# IO_ENC.net
KiCad netlist of a schematic drawn in Altium Designer
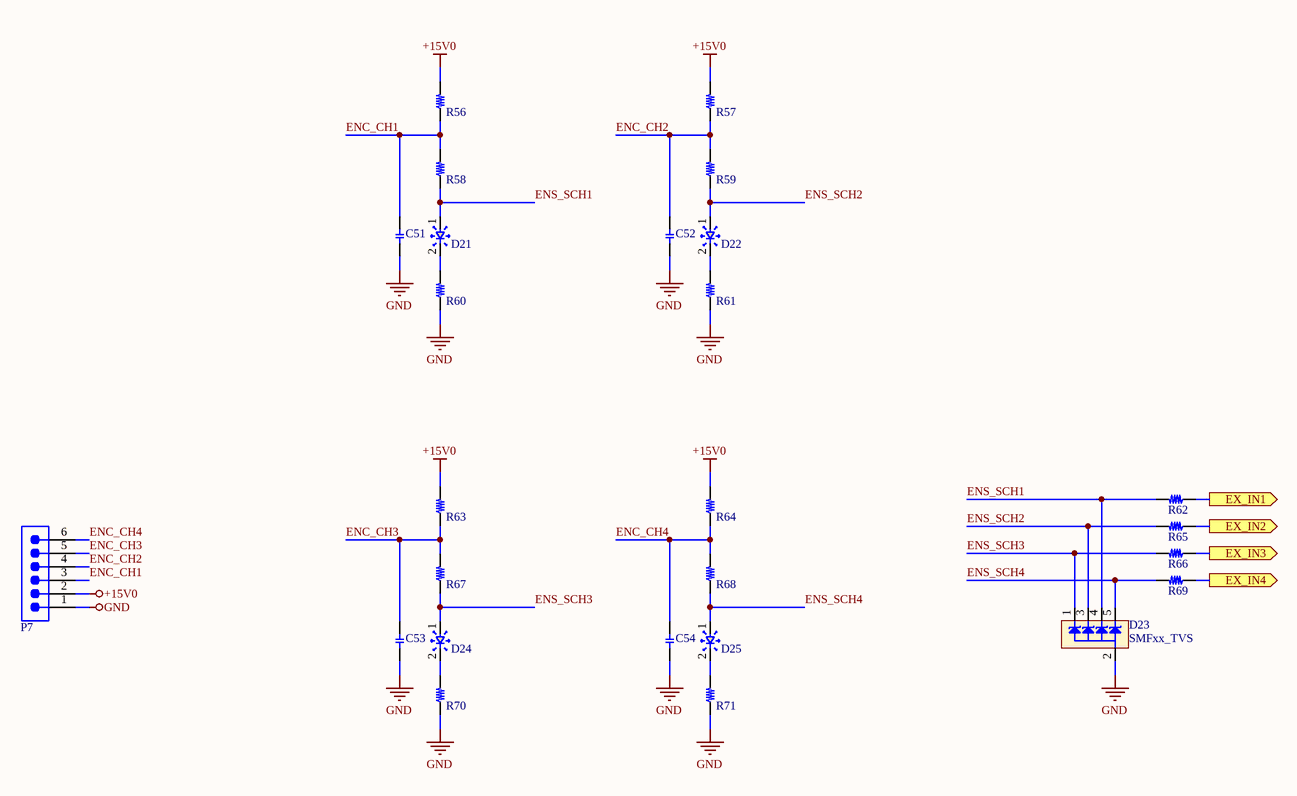
[diagram p0: IO_ENC.SchDoc]

(export (version "E")
  (design (tool "Eeschema 10.0.6"))
  (components
    (comp (ref "C51")
      (value "CAP_SMD")
      (footprint "C 0603")
      (libsource (lib "radmehr_library") (part "CAP_SMD"))
    )
    (comp (ref "C52")
      (value "CAP_SMD")
      (footprint "C 0603")
      (libsource (lib "radmehr_library") (part "CAP_SMD"))
    )
    (comp (ref "C53")
      (value "CAP_SMD")
      (footprint "C 0603")
      (libsource (lib "radmehr_library") (part "CAP_SMD"))
    )
    (comp (ref "C54")
      (value "CAP_SMD")
      (footprint "C 0603")
      (libsource (lib "radmehr_library") (part "CAP_SMD"))
    )
    (comp (ref "D21")
      (value "LED_SMD")
      (footprint "D 0603")
      (libsource (lib "radmehr_library") (part "LED_SMD"))
    )
    (comp (ref "D22")
      (value "LED_SMD")
      (footprint "D 0603")
      (libsource (lib "radmehr_library") (part "LED_SMD"))
    )
    (comp (ref "D23")
      (value "SMFxx_TVS")
      (footprint "SOT353-5")
      (libsource (lib "radmehr_library") (part "SMFxx_TVS"))
    )
    (comp (ref "D24")
      (value "LED_SMD")
      (footprint "D 0603")
      (libsource (lib "radmehr_library") (part "LED_SMD"))
    )
    (comp (ref "D25")
      (value "LED_SMD")
      (footprint "D 0603")
      (libsource (lib "radmehr_library") (part "LED_SMD"))
    )
    (comp (ref "P7")
      (value "691321300006")
      (footprint "691321300006")
      (description "WR-TBL Series 321 Vertical PCB Header, Through Hole, pitch 3.81mm, 6p")
      (fields (field (name "MANUFACTURER") "Wurth Elektronik"))
      (libsource (lib "Altium_WR-TBL (rev22a)") (part "691321300006"))
    )
    (comp (ref "R56")
      (value "RES_SMD")
      (footprint "R 1206")
      (libsource (lib "radmehr_library") (part "RES_SMD"))
    )
    (comp (ref "R57")
      (value "RES_SMD")
      (footprint "R 1206")
      (libsource (lib "radmehr_library") (part "RES_SMD"))
    )
    (comp (ref "R58")
      (value "RES_SMD")
      (footprint "R 0603")
      (libsource (lib "radmehr_library") (part "RES_SMD"))
    )
    (comp (ref "R59")
      (value "RES_SMD")
      (footprint "R 0603")
      (libsource (lib "radmehr_library") (part "RES_SMD"))
    )
    (comp (ref "R60")
      (value "RES_SMD")
      (footprint "R 0603")
      (libsource (lib "radmehr_library") (part "RES_SMD"))
    )
    (comp (ref "R61")
      (value "RES_SMD")
      (footprint "R 0603")
      (libsource (lib "radmehr_library") (part "RES_SMD"))
    )
    (comp (ref "R62")
      (value "RES_SMD")
      (footprint "R 0603")
      (libsource (lib "radmehr_library") (part "RES_SMD"))
    )
    (comp (ref "R63")
      (value "RES_SMD")
      (footprint "R 1206")
      (libsource (lib "radmehr_library") (part "RES_SMD"))
    )
    (comp (ref "R64")
      (value "RES_SMD")
      (footprint "R 1206")
      (libsource (lib "radmehr_library") (part "RES_SMD"))
    )
    (comp (ref "R65")
      (value "RES_SMD")
      (footprint "R 0603")
      (libsource (lib "radmehr_library") (part "RES_SMD"))
    )
    (comp (ref "R66")
      (value "RES_SMD")
      (footprint "R 0603")
      (libsource (lib "radmehr_library") (part "RES_SMD"))
    )
    (comp (ref "R67")
      (value "RES_SMD")
      (footprint "R 0603")
      (libsource (lib "radmehr_library") (part "RES_SMD"))
    )
    (comp (ref "R68")
      (value "RES_SMD")
      (footprint "R 0603")
      (libsource (lib "radmehr_library") (part "RES_SMD"))
    )
    (comp (ref "R69")
      (value "RES_SMD")
      (footprint "R 0603")
      (libsource (lib "radmehr_library") (part "RES_SMD"))
    )
    (comp (ref "R70")
      (value "RES_SMD")
      (footprint "R 0603")
      (libsource (lib "radmehr_library") (part "RES_SMD"))
    )
    (comp (ref "R71")
      (value "RES_SMD")
      (footprint "R 0603")
      (libsource (lib "radmehr_library") (part "RES_SMD"))
    )
  )
  (nets
    (net (code "1") (name "+15V0") (class "Default")
      (node (ref "P7") (pin "2") (pinfunction "2_2") (pintype "passive"))
      (node (ref "R56") (pin "2") (pinfunction "2_2") (pintype "passive"))
      (node (ref "R57") (pin "2") (pinfunction "2_2") (pintype "passive"))
      (node (ref "R63") (pin "2") (pinfunction "2_2") (pintype "passive"))
      (node (ref "R64") (pin "2") (pinfunction "2_2") (pintype "passive"))
    )
    (net (code "2") (name "/ENC_CH1") (class "Default")
      (node (ref "C51") (pin "2") (pinfunction "2_2") (pintype "passive"))
      (node (ref "P7") (pin "3") (pinfunction "3_3") (pintype "passive"))
      (node (ref "R56") (pin "1") (pinfunction "1_1") (pintype "passive"))
      (node (ref "R58") (pin "2") (pinfunction "2_2") (pintype "passive"))
    )
    (net (code "3") (name "/ENC_CH2") (class "Default")
      (node (ref "C52") (pin "2") (pinfunction "2_2") (pintype "passive"))
      (node (ref "P7") (pin "4") (pinfunction "4_4") (pintype "passive"))
      (node (ref "R57") (pin "1") (pinfunction "1_1") (pintype "passive"))
      (node (ref "R59") (pin "2") (pinfunction "2_2") (pintype "passive"))
    )
    (net (code "4") (name "/ENC_CH3") (class "Default")
      (node (ref "C53") (pin "2") (pinfunction "2_2") (pintype "passive"))
      (node (ref "P7") (pin "5") (pinfunction "5_5") (pintype "passive"))
      (node (ref "R63") (pin "1") (pinfunction "1_1") (pintype "passive"))
      (node (ref "R67") (pin "2") (pinfunction "2_2") (pintype "passive"))
    )
    (net (code "5") (name "/ENC_CH4") (class "Default")
      (node (ref "C54") (pin "2") (pinfunction "2_2") (pintype "passive"))
      (node (ref "P7") (pin "6") (pinfunction "6_6") (pintype "passive"))
      (node (ref "R64") (pin "1") (pinfunction "1_1") (pintype "passive"))
      (node (ref "R68") (pin "2") (pinfunction "2_2") (pintype "passive"))
    )
    (net (code "6") (name "/ENS_SCH1") (class "Default")
      (node (ref "D21") (pin "1") (pintype "passive"))
      (node (ref "D23") (pin "4") (pinfunction "K3_4") (pintype "passive"))
      (node (ref "R58") (pin "1") (pinfunction "1_1") (pintype "passive"))
      (node (ref "R62") (pin "2") (pinfunction "2_2") (pintype "passive"))
    )
    (net (code "7") (name "/ENS_SCH2") (class "Default")
      (node (ref "D22") (pin "1") (pintype "passive"))
      (node (ref "D23") (pin "3") (pinfunction "K2_3") (pintype "passive"))
      (node (ref "R59") (pin "1") (pinfunction "1_1") (pintype "passive"))
      (node (ref "R65") (pin "2") (pinfunction "2_2") (pintype "passive"))
    )
    (net (code "8") (name "/ENS_SCH3") (class "Default")
      (node (ref "D23") (pin "1") (pinfunction "K1_1") (pintype "passive"))
      (node (ref "D24") (pin "1") (pintype "passive"))
      (node (ref "R66") (pin "2") (pinfunction "2_2") (pintype "passive"))
      (node (ref "R67") (pin "1") (pinfunction "1_1") (pintype "passive"))
    )
    (net (code "9") (name "/ENS_SCH4") (class "Default")
      (node (ref "D23") (pin "5") (pinfunction "K4_5") (pintype "passive"))
      (node (ref "D25") (pin "1") (pintype "passive"))
      (node (ref "R68") (pin "1") (pinfunction "1_1") (pintype "passive"))
      (node (ref "R69") (pin "2") (pinfunction "2_2") (pintype "passive"))
    )
    (net (code "10") (name "/EX_IN1") (class "Default")
      (node (ref "R62") (pin "1") (pinfunction "1_1") (pintype "passive"))
    )
    (net (code "11") (name "/EX_IN2") (class "Default")
      (node (ref "R65") (pin "1") (pinfunction "1_1") (pintype "passive"))
    )
    (net (code "12") (name "/EX_IN3") (class "Default")
      (node (ref "R66") (pin "1") (pinfunction "1_1") (pintype "passive"))
    )
    (net (code "13") (name "/EX_IN4") (class "Default")
      (node (ref "R69") (pin "1") (pinfunction "1_1") (pintype "passive"))
    )
    (net (code "14") (name "GND") (class "Default")
      (node (ref "C51") (pin "1") (pinfunction "1_1") (pintype "passive"))
      (node (ref "C52") (pin "1") (pinfunction "1_1") (pintype "passive"))
      (node (ref "C53") (pin "1") (pinfunction "1_1") (pintype "passive"))
      (node (ref "C54") (pin "1") (pinfunction "1_1") (pintype "passive"))
      (node (ref "D23") (pin "2") (pinfunction "GND_2") (pintype "passive"))
      (node (ref "P7") (pin "1") (pinfunction "1_1") (pintype "passive"))
      (node (ref "R60") (pin "1") (pinfunction "1_1") (pintype "passive"))
      (node (ref "R61") (pin "1") (pinfunction "1_1") (pintype "passive"))
      (node (ref "R70") (pin "1") (pinfunction "1_1") (pintype "passive"))
      (node (ref "R71") (pin "1") (pinfunction "1_1") (pintype "passive"))
    )
    (net (code "15") (name "Net-(D21-Pad2)") (class "Default")
      (node (ref "D21") (pin "2") (pintype "passive"))
      (node (ref "R60") (pin "2") (pinfunction "2_2") (pintype "passive"))
    )
    (net (code "16") (name "Net-(D22-Pad2)") (class "Default")
      (node (ref "D22") (pin "2") (pintype "passive"))
      (node (ref "R61") (pin "2") (pinfunction "2_2") (pintype "passive"))
    )
    (net (code "17") (name "Net-(D24-Pad2)") (class "Default")
      (node (ref "D24") (pin "2") (pintype "passive"))
      (node (ref "R70") (pin "2") (pinfunction "2_2") (pintype "passive"))
    )
    (net (code "18") (name "Net-(D25-Pad2)") (class "Default")
      (node (ref "D25") (pin "2") (pintype "passive"))
      (node (ref "R71") (pin "2") (pinfunction "2_2") (pintype "passive"))
    )
  )
)
